# Intermediate_LCL_Top_20230320.net
KiCad netlist of a schematic drawn in Altium Designer
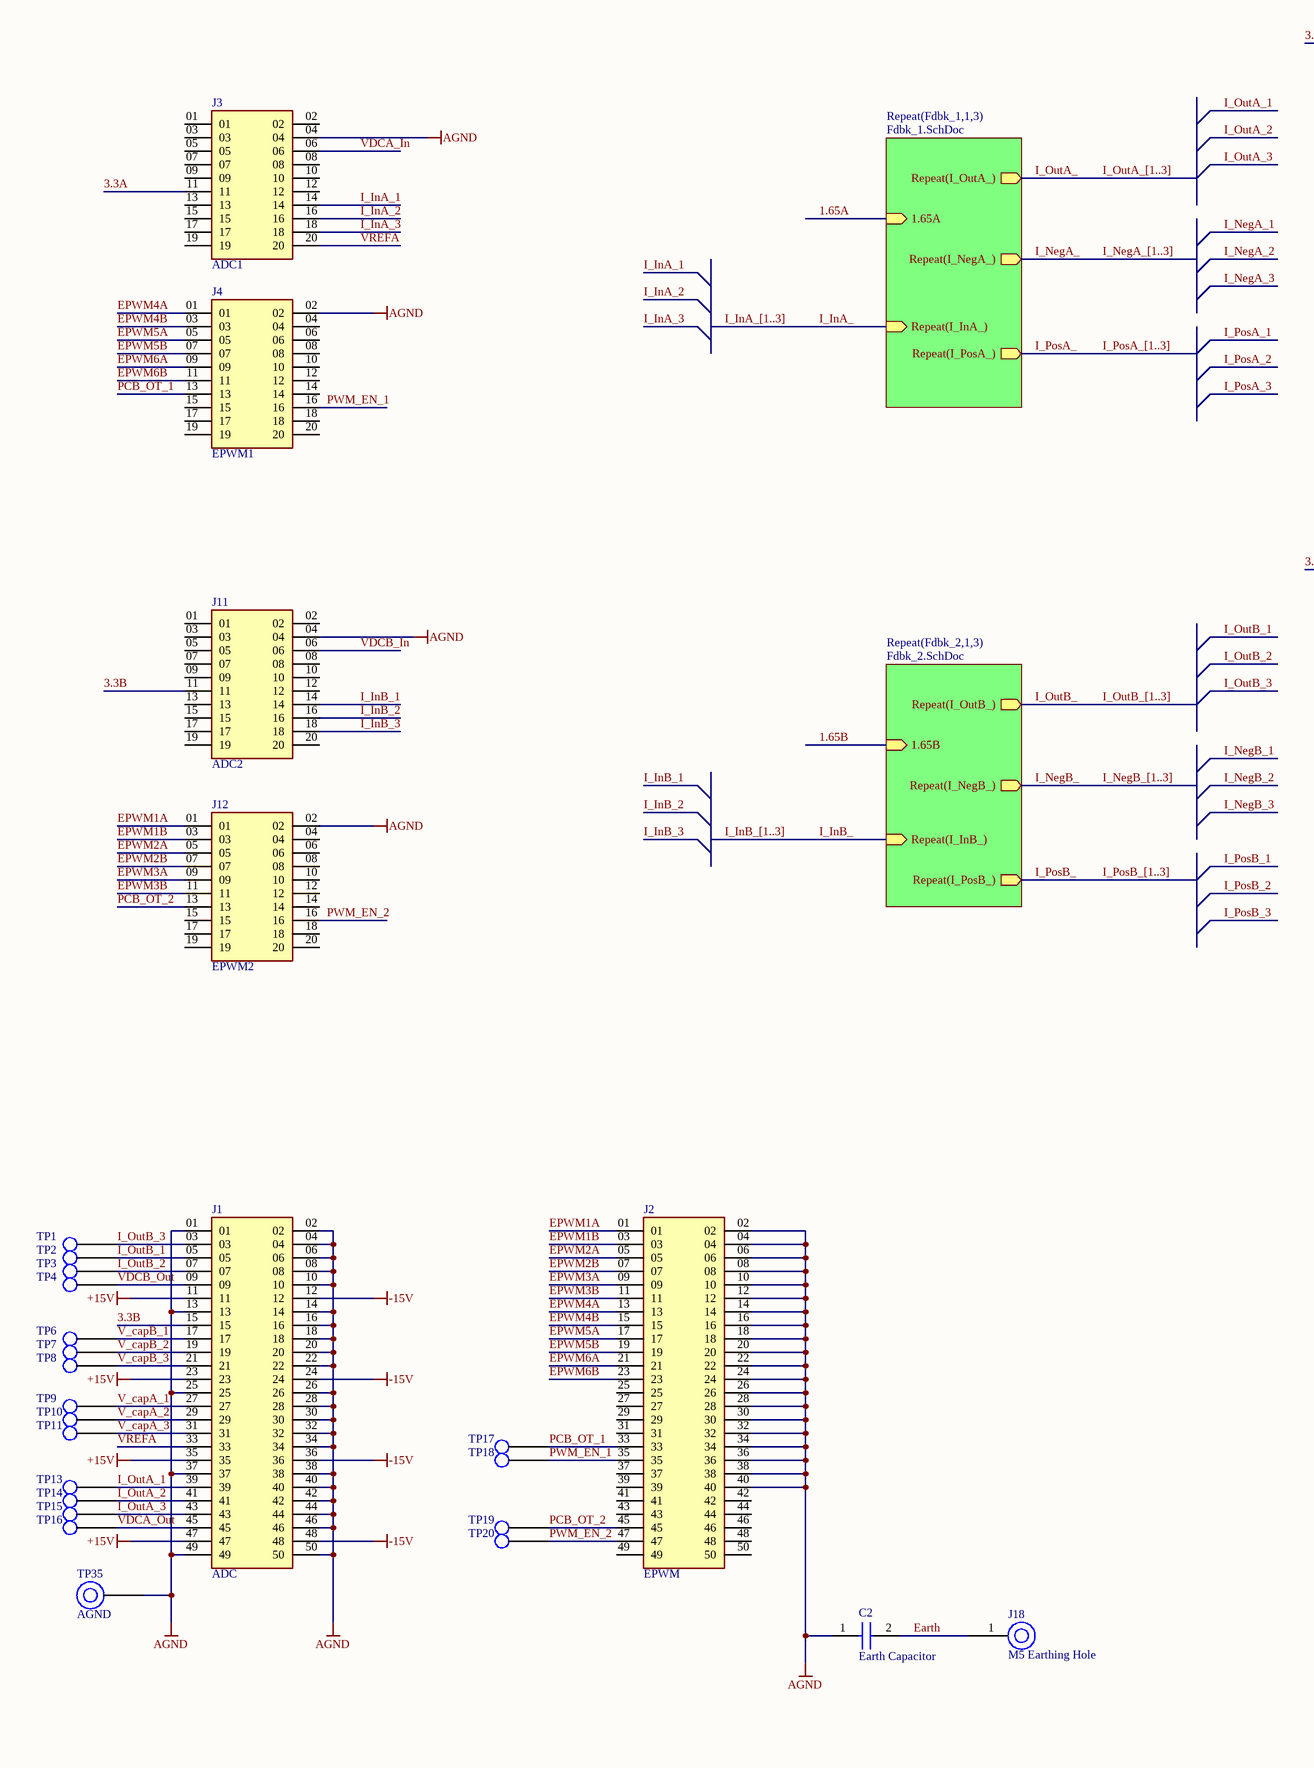
[diagram p0: Intermediate_LCL_Top_20230320.SchDoc, left]
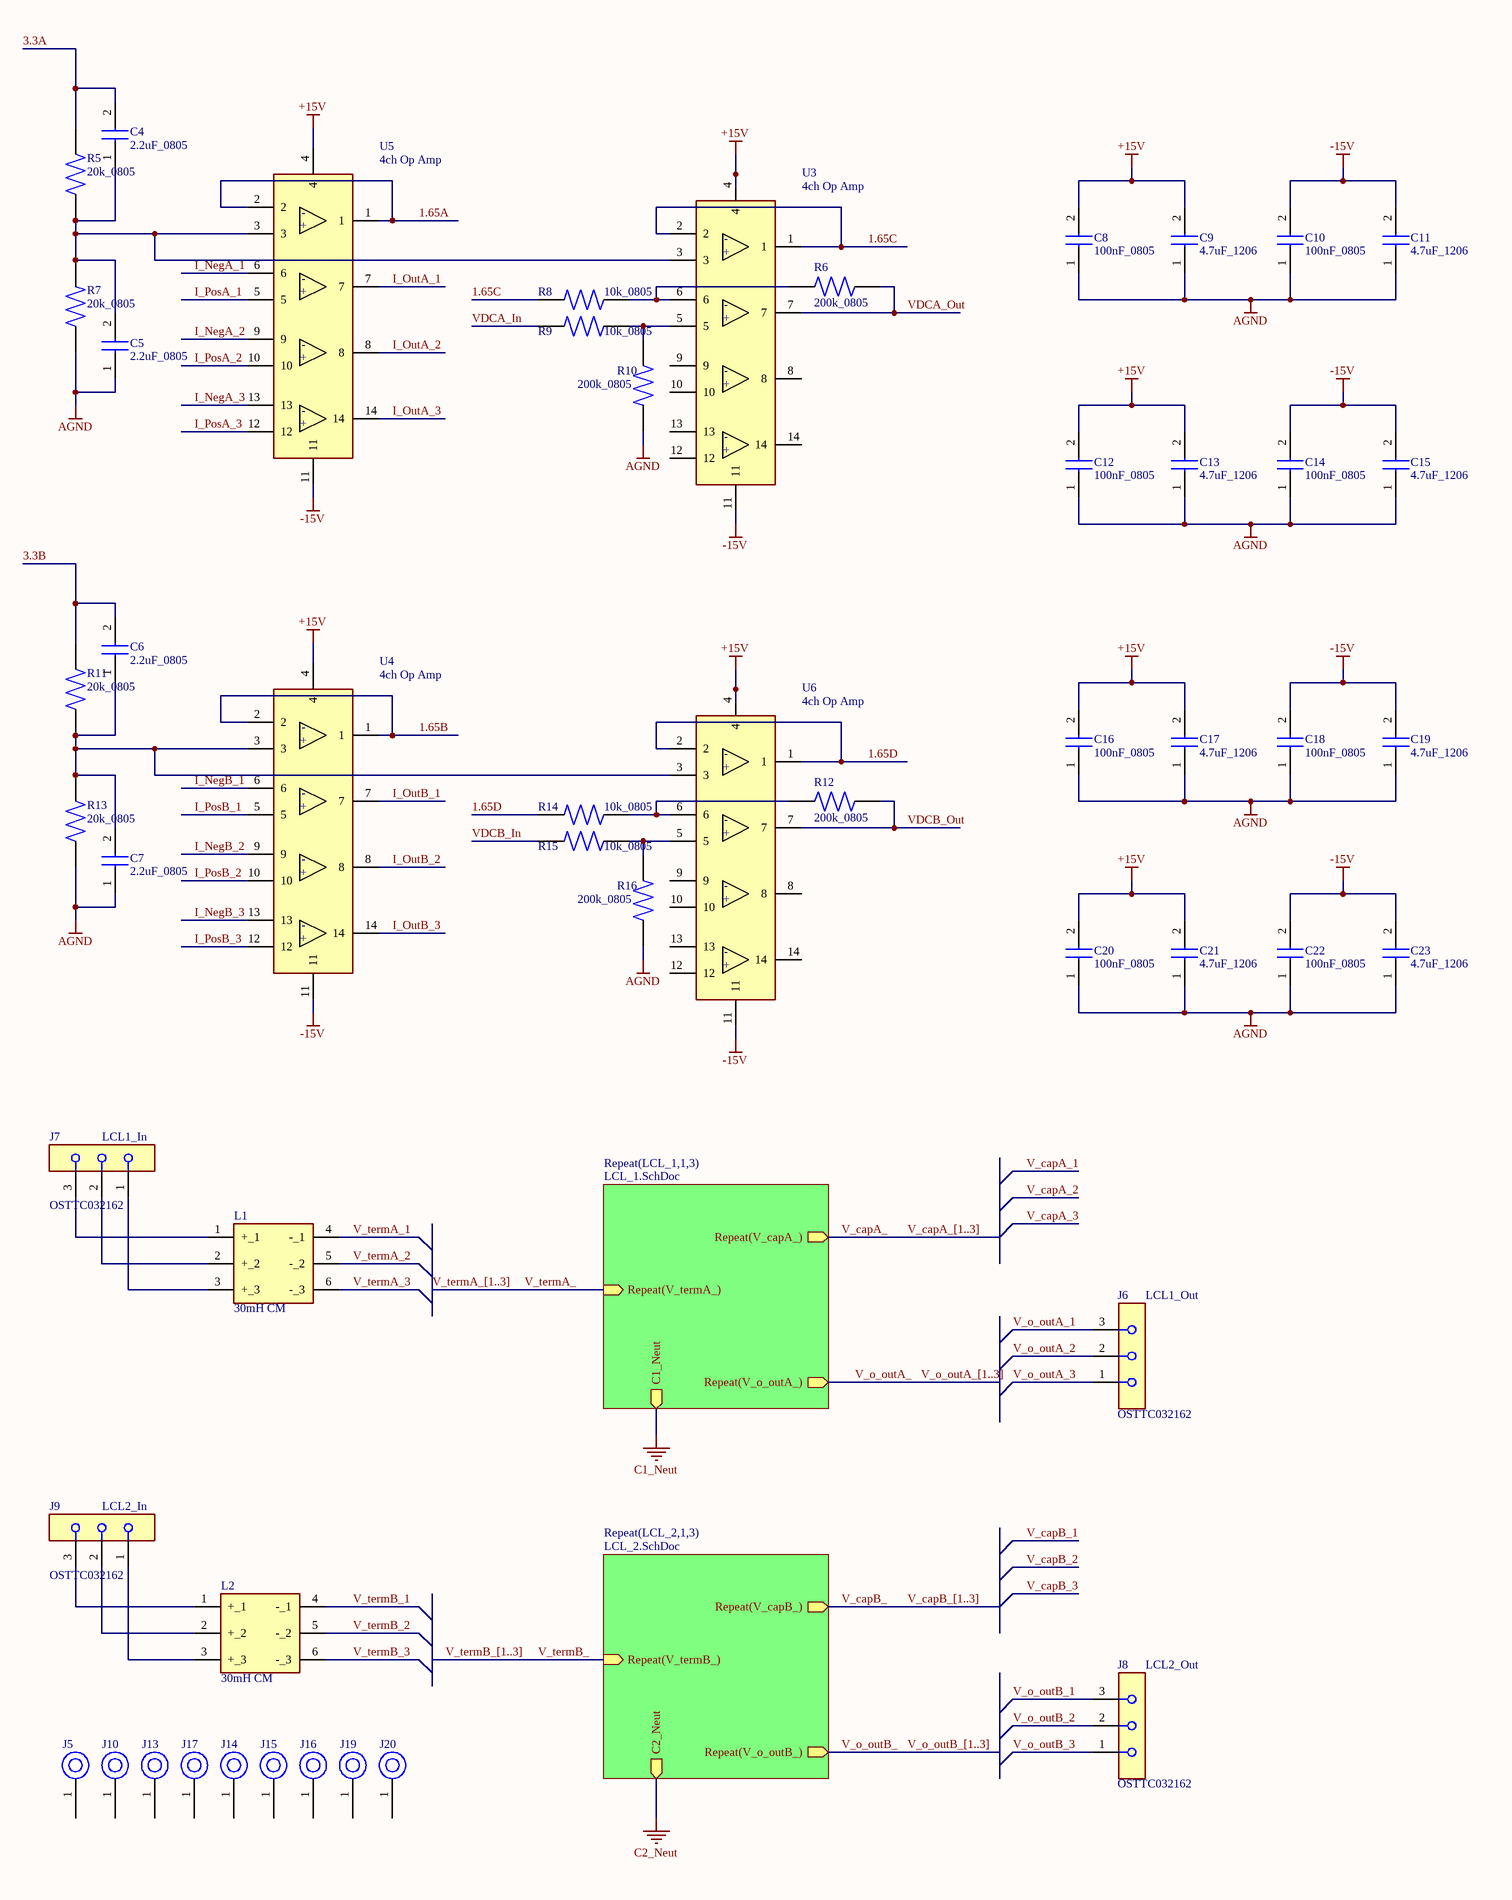
[diagram p1: Intermediate_LCL_Top_20230320.SchDoc, right]

(export (version "E")
  (design (tool "Eeschema 10.0.6"))
  (components
    (comp (ref "C2")
      (value "Earth Capacitor")
      (footprint "RAD-0.3")
      (description "Y Earth Capacitor")
      (fields (field (name "MP") "C1206C120J5GACTU"))
      (libsource (lib "FYP_Components") (part "102_Y"))
    )
    (comp (ref "C4")
      (value "2.2uF_0805")
      (footprint "0805 Capacitor")
      (description "SMD Multilayer Ceramic Capacitor, 2.2 µF, 50 V, 0805 [2012 Metric], ± 10%, X5R, C")
      (libsource (lib "FYP_Components") (part "C2012X5R1H225K125AB"))
    )
    (comp (ref "C5")
      (value "2.2uF_0805")
      (footprint "0805 Capacitor")
      (description "SMD Multilayer Ceramic Capacitor, 2.2 µF, 50 V, 0805 [2012 Metric], ± 10%, X5R, C")
      (libsource (lib "FYP_Components") (part "C2012X5R1H225K125AB"))
    )
    (comp (ref "C6")
      (value "2.2uF_0805")
      (footprint "0805 Capacitor")
      (description "SMD Multilayer Ceramic Capacitor, 2.2 µF, 50 V, 0805 [2012 Metric], ± 10%, X5R, C")
      (libsource (lib "FYP_Components") (part "C2012X5R1H225K125AB"))
    )
    (comp (ref "C7")
      (value "2.2uF_0805")
      (footprint "0805 Capacitor")
      (description "SMD Multilayer Ceramic Capacitor, 2.2 µF, 50 V, 0805 [2012 Metric], ± 10%, X5R, C")
      (libsource (lib "FYP_Components") (part "C2012X5R1H225K125AB"))
    )
    (comp (ref "C8")
      (value "100nF_0805")
      (footprint "0805 Capacitor")
      (description "SMD Multilayer Ceramic Capacitor, 0.1 µF, 50 V, 0805 [2012 Metric], ± 5%, X7R, C Series KEMET")
      (libsource (lib "FYP_Components") (part "C0805C104J5RACTU"))
    )
    (comp (ref "C9")
      (value "4.7uF_1206")
      (footprint "FYP_Components:1206 Capacitor")
      (description "SMD Multilayer Ceramic Capacitor, 4.7 µF, 50 V, 1206 [3216 Metric], ± 10%, X7R, C")
      (fields (field (name "MP") "C1206C120J5GACTU"))
      (libsource (lib "FYP_Components") (part "C3216X7R1H475K160AC"))
    )
    (comp (ref "C10")
      (value "100nF_0805")
      (footprint "0805 Capacitor")
      (description "SMD Multilayer Ceramic Capacitor, 0.1 µF, 50 V, 0805 [2012 Metric], ± 5%, X7R, C Series KEMET")
      (libsource (lib "FYP_Components") (part "C0805C104J5RACTU"))
    )
    (comp (ref "C11")
      (value "4.7uF_1206")
      (footprint "FYP_Components:1206 Capacitor")
      (description "SMD Multilayer Ceramic Capacitor, 4.7 µF, 50 V, 1206 [3216 Metric], ± 10%, X7R, C")
      (fields (field (name "MP") "C1206C120J5GACTU"))
      (libsource (lib "FYP_Components") (part "C3216X7R1H475K160AC"))
    )
    (comp (ref "C12")
      (value "100nF_0805")
      (footprint "0805 Capacitor")
      (description "SMD Multilayer Ceramic Capacitor, 0.1 µF, 50 V, 0805 [2012 Metric], ± 5%, X7R, C Series KEMET")
      (libsource (lib "FYP_Components") (part "C0805C104J5RACTU"))
    )
    (comp (ref "C13")
      (value "4.7uF_1206")
      (footprint "FYP_Components:1206 Capacitor")
      (description "SMD Multilayer Ceramic Capacitor, 4.7 µF, 50 V, 1206 [3216 Metric], ± 10%, X7R, C")
      (fields (field (name "MP") "C1206C120J5GACTU"))
      (libsource (lib "FYP_Components") (part "C3216X7R1H475K160AC"))
    )
    (comp (ref "C14")
      (value "100nF_0805")
      (footprint "0805 Capacitor")
      (description "SMD Multilayer Ceramic Capacitor, 0.1 µF, 50 V, 0805 [2012 Metric], ± 5%, X7R, C Series KEMET")
      (libsource (lib "FYP_Components") (part "C0805C104J5RACTU"))
    )
    (comp (ref "C15")
      (value "4.7uF_1206")
      (footprint "FYP_Components:1206 Capacitor")
      (description "SMD Multilayer Ceramic Capacitor, 4.7 µF, 50 V, 1206 [3216 Metric], ± 10%, X7R, C")
      (fields (field (name "MP") "C1206C120J5GACTU"))
      (libsource (lib "FYP_Components") (part "C3216X7R1H475K160AC"))
    )
    (comp (ref "C16")
      (value "100nF_0805")
      (footprint "0805 Capacitor")
      (description "SMD Multilayer Ceramic Capacitor, 0.1 µF, 50 V, 0805 [2012 Metric], ± 5%, X7R, C Series KEMET")
      (libsource (lib "FYP_Components") (part "C0805C104J5RACTU"))
    )
    (comp (ref "C17")
      (value "4.7uF_1206")
      (footprint "FYP_Components:1206 Capacitor")
      (description "SMD Multilayer Ceramic Capacitor, 4.7 µF, 50 V, 1206 [3216 Metric], ± 10%, X7R, C")
      (fields (field (name "MP") "C1206C120J5GACTU"))
      (libsource (lib "FYP_Components") (part "C3216X7R1H475K160AC"))
    )
    (comp (ref "C18")
      (value "100nF_0805")
      (footprint "0805 Capacitor")
      (description "SMD Multilayer Ceramic Capacitor, 0.1 µF, 50 V, 0805 [2012 Metric], ± 5%, X7R, C Series KEMET")
      (libsource (lib "FYP_Components") (part "C0805C104J5RACTU"))
    )
    (comp (ref "C19")
      (value "4.7uF_1206")
      (footprint "FYP_Components:1206 Capacitor")
      (description "SMD Multilayer Ceramic Capacitor, 4.7 µF, 50 V, 1206 [3216 Metric], ± 10%, X7R, C")
      (fields (field (name "MP") "C1206C120J5GACTU"))
      (libsource (lib "FYP_Components") (part "C3216X7R1H475K160AC"))
    )
    (comp (ref "C20")
      (value "100nF_0805")
      (footprint "0805 Capacitor")
      (description "SMD Multilayer Ceramic Capacitor, 0.1 µF, 50 V, 0805 [2012 Metric], ± 5%, X7R, C Series KEMET")
      (libsource (lib "FYP_Components") (part "C0805C104J5RACTU"))
    )
    (comp (ref "C21")
      (value "4.7uF_1206")
      (footprint "FYP_Components:1206 Capacitor")
      (description "SMD Multilayer Ceramic Capacitor, 4.7 µF, 50 V, 1206 [3216 Metric], ± 10%, X7R, C")
      (fields (field (name "MP") "C1206C120J5GACTU"))
      (libsource (lib "FYP_Components") (part "C3216X7R1H475K160AC"))
    )
    (comp (ref "C22")
      (value "100nF_0805")
      (footprint "0805 Capacitor")
      (description "SMD Multilayer Ceramic Capacitor, 0.1 µF, 50 V, 0805 [2012 Metric], ± 5%, X7R, C Series KEMET")
      (libsource (lib "FYP_Components") (part "C0805C104J5RACTU"))
    )
    (comp (ref "C23")
      (value "4.7uF_1206")
      (footprint "FYP_Components:1206 Capacitor")
      (description "SMD Multilayer Ceramic Capacitor, 4.7 µF, 50 V, 1206 [3216 Metric], ± 10%, X7R, C")
      (fields (field (name "MP") "C1206C120J5GACTU"))
      (libsource (lib "FYP_Components") (part "C3216X7R1H475K160AC"))
    )
    (comp (ref "J1")
      (value "ADC")
      (footprint "SHF-125-01-L-D-RA")
      (description "50-Pin Simplus Connector")
      (fields (field (name "MP") "SHF-125-01-L-D-RA") (field (name "MF") "Samtec"))
      (libsource (lib "FYP_Components") (part "SHF-125-01-L-D-RA"))
    )
    (comp (ref "J2")
      (value "EPWM")
      (footprint "SHF-125-01-L-D-RA")
      (description "50-Pin Simplus Connector")
      (fields (field (name "MP") "SHF-125-01-L-D-RA") (field (name "MF") "Samtec"))
      (libsource (lib "FYP_Components") (part "SHF-125-01-L-D-RA"))
    )
    (comp (ref "J3")
      (value "ADC1")
      (footprint "FYP_Components:SSQ-110-03-T-D")
      (description "SSQ - Samtec 2.54mm Square Tail Dual Row Socket Strip 8.5mm Profile - Fast Stock")
      (fields (field (name "MF") "Samtec Inc.") (field (name "MP") "SSQ-110-03-T-D"))
      (libsource (lib "FYP_Components") (part "SSQ-110-03-T-D"))
    )
    (comp (ref "J4")
      (value "EPWM1")
      (footprint "FYP_Components:SSQ-110-03-T-D")
      (description "SSQ - Samtec 2.54mm Square Tail Dual Row Socket Strip 8.5mm Profile - Fast Stock")
      (fields (field (name "MF") "Samtec Inc.") (field (name "MP") "SSQ-110-03-T-D"))
      (libsource (lib "FYP_Components") (part "SSQ-110-03-T-D"))
    )
    (comp (ref "J5")
      (value "M5 Mounting Hole")
      (footprint "M5 Mounting Hole")
      (libsource (lib "FYP_Components") (part "M5 Mounting Hole"))
    )
    (comp (ref "J6")
      (value "LCL1_Out")
      (footprint "3 Pin Terminal")
      (description "3 Position Terminal Block 5.08mm")
      (fields
        (field (name "VOLTAGE") "300V")
        (field (name "MANUFACTURER") "On Shore Technology")
        (field (name "PART NUMBER") "OSTTC032162")
      )
      (libsource (lib "FYP_Components") (part "3PinTerminal"))
    )
    (comp (ref "J7")
      (value "LCL1_In")
      (footprint "3 Pin Terminal")
      (description "3 Position Terminal Block 5.08mm")
      (fields
        (field (name "VOLTAGE") "300V")
        (field (name "MANUFACTURER") "On Shore Technology")
        (field (name "PART NUMBER") "OSTTC032162")
      )
      (libsource (lib "") (part "3PinTerminal_1"))
    )
    (comp (ref "J8")
      (value "LCL2_Out")
      (footprint "3 Pin Terminal")
      (description "3 Position Terminal Block 5.08mm")
      (fields
        (field (name "VOLTAGE") "300V")
        (field (name "MANUFACTURER") "On Shore Technology")
        (field (name "PART NUMBER") "OSTTC032162")
      )
      (libsource (lib "FYP_Components") (part "3PinTerminal"))
    )
    (comp (ref "J9")
      (value "LCL2_In")
      (footprint "3 Pin Terminal")
      (description "3 Position Terminal Block 5.08mm")
      (fields
        (field (name "VOLTAGE") "300V")
        (field (name "MANUFACTURER") "On Shore Technology")
        (field (name "PART NUMBER") "OSTTC032162")
      )
      (libsource (lib "") (part "3PinTerminal_1"))
    )
    (comp (ref "J10")
      (value "M5 Mounting Hole")
      (footprint "M5 Mounting Hole")
      (libsource (lib "FYP_Components") (part "M5 Mounting Hole"))
    )
    (comp (ref "J11")
      (value "ADC2")
      (footprint "FYP_Components:SSQ-110-03-T-D")
      (description "SSQ - Samtec 2.54mm Square Tail Dual Row Socket Strip 8.5mm Profile - Fast Stock")
      (fields (field (name "MF") "Samtec Inc.") (field (name "MP") "SSQ-110-03-T-D"))
      (libsource (lib "FYP_Components") (part "SSQ-110-03-T-D"))
    )
    (comp (ref "J12")
      (value "EPWM2")
      (footprint "FYP_Components:SSQ-110-03-T-D")
      (description "SSQ - Samtec 2.54mm Square Tail Dual Row Socket Strip 8.5mm Profile - Fast Stock")
      (fields (field (name "MF") "Samtec Inc.") (field (name "MP") "SSQ-110-03-T-D"))
      (libsource (lib "FYP_Components") (part "SSQ-110-03-T-D"))
    )
    (comp (ref "J13")
      (value "M5 Mounting Hole")
      (footprint "M5 Mounting Hole")
      (libsource (lib "FYP_Components") (part "M5 Mounting Hole"))
    )
    (comp (ref "J14")
      (value "M5 Mounting Hole")
      (footprint "M5 Mounting Hole")
      (libsource (lib "FYP_Components") (part "M5 Mounting Hole"))
    )
    (comp (ref "J15")
      (value "M5 Mounting Hole")
      (footprint "M5 Mounting Hole")
      (libsource (lib "FYP_Components") (part "M5 Mounting Hole"))
    )
    (comp (ref "J16")
      (value "M5 Mounting Hole")
      (footprint "M5 Mounting Hole")
      (libsource (lib "FYP_Components") (part "M5 Mounting Hole"))
    )
    (comp (ref "J17")
      (value "M5 Mounting Hole")
      (footprint "M5 Mounting Hole")
      (libsource (lib "FYP_Components") (part "M5 Mounting Hole"))
    )
    (comp (ref "J18")
      (value "M5 Earthing Hole")
      (footprint "M5 Earthing Hole")
      (libsource (lib "FYP_Components") (part "M5 Earthing Hole"))
    )
    (comp (ref "J19")
      (value "M5 Mounting Hole")
      (footprint "M5 Mounting Hole")
      (libsource (lib "FYP_Components") (part "M5 Mounting Hole"))
    )
    (comp (ref "J20")
      (value "M5 Mounting Hole")
      (footprint "M5 Mounting Hole")
      (libsource (lib "FYP_Components") (part "M5 Mounting Hole"))
    )
    (comp (ref "L1")
      (value "30mH CM")
      (footprint "FYP_Components:CM Choke Custom")
      (description "30mH Custom CM Choke")
      (fields
        (field (name "MANUFACTURER_PART_NUMBER") "744839029220")
        (field (name "MOUSER PART NUMBER") "710-744839029220")
      )
      (libsource (lib "FYP_Components") (part "30mH Custom CM Choke"))
    )
    (comp (ref "L2")
      (value "30mH CM")
      (footprint "FYP_Components:CM Choke Custom")
      (description "30mH Custom CM Choke")
      (fields
        (field (name "MANUFACTURER_PART_NUMBER") "744839029220")
        (field (name "MOUSER PART NUMBER") "710-744839029220")
      )
      (libsource (lib "FYP_Components") (part "30mH Custom CM Choke"))
    )
    (comp (ref "R5")
      (value "20k_0805")
      (footprint "FYP_Components:0805 Resistor")
      (description "SMD Chip Resistor, 20 kohm, ± 1%, 125 mW, 0805 [2012 Metric], Thick Film, General Purpose")
      (fields (field (name "MF") "Bourns") (field (name "MP") "CRE2512-FZ-R007E-3"))
      (libsource (lib "FYP_Components") (part "CRCW080520K0FKEA"))
    )
    (comp (ref "R6")
      (value "200k_0805")
      (footprint "FYP_Components:0805 Resistor")
      (description "SMD Chip Resistor, 200 kohm, ± 1%, 125 mW, 0805 [2012 Metric], Thick Film, General Purpose")
      (fields (field (name "MF") "Bourns") (field (name "MP") "CRE2512-FZ-R007E-3"))
      (libsource (lib "FYP_Components") (part "CRCW0805200KFKEA"))
    )
    (comp (ref "R7")
      (value "20k_0805")
      (footprint "FYP_Components:0805 Resistor")
      (description "SMD Chip Resistor, 20 kohm, ± 1%, 125 mW, 0805 [2012 Metric], Thick Film, General Purpose")
      (fields (field (name "MF") "Bourns") (field (name "MP") "CRE2512-FZ-R007E-3"))
      (libsource (lib "FYP_Components") (part "CRCW080520K0FKEA"))
    )
    (comp (ref "R8")
      (value "10k_0805")
      (footprint "FYP_Components:0805 Resistor")
      (description "SMD Chip Resistor, 10 kohm, ± 1%, 125 mW, 0805 [2012 Metric], Thick Film, General Purpose")
      (fields (field (name "MF") "Bourns") (field (name "MP") "CRE2512-FZ-R007E-3"))
      (libsource (lib "FYP_Components") (part "CRCW080510K0FKEA"))
    )
    (comp (ref "R9")
      (value "10k_0805")
      (footprint "FYP_Components:0805 Resistor")
      (description "SMD Chip Resistor, 10 kohm, ± 1%, 125 mW, 0805 [2012 Metric], Thick Film, General Purpose")
      (fields (field (name "MF") "Bourns") (field (name "MP") "CRE2512-FZ-R007E-3"))
      (libsource (lib "FYP_Components") (part "CRCW080510K0FKEA"))
    )
    (comp (ref "R10")
      (value "200k_0805")
      (footprint "FYP_Components:0805 Resistor")
      (description "SMD Chip Resistor, 200 kohm, ± 1%, 125 mW, 0805 [2012 Metric], Thick Film, General Purpose")
      (fields (field (name "MF") "Bourns") (field (name "MP") "CRE2512-FZ-R007E-3"))
      (libsource (lib "FYP_Components") (part "CRCW0805200KFKEA"))
    )
    (comp (ref "R11")
      (value "20k_0805")
      (footprint "FYP_Components:0805 Resistor")
      (description "SMD Chip Resistor, 20 kohm, ± 1%, 125 mW, 0805 [2012 Metric], Thick Film, General Purpose")
      (fields (field (name "MF") "Bourns") (field (name "MP") "CRE2512-FZ-R007E-3"))
      (libsource (lib "FYP_Components") (part "CRCW080520K0FKEA"))
    )
    (comp (ref "R12")
      (value "200k_0805")
      (footprint "FYP_Components:0805 Resistor")
      (description "SMD Chip Resistor, 200 kohm, ± 1%, 125 mW, 0805 [2012 Metric], Thick Film, General Purpose")
      (fields (field (name "MF") "Bourns") (field (name "MP") "CRE2512-FZ-R007E-3"))
      (libsource (lib "FYP_Components") (part "CRCW0805200KFKEA"))
    )
    (comp (ref "R13")
      (value "20k_0805")
      (footprint "FYP_Components:0805 Resistor")
      (description "SMD Chip Resistor, 20 kohm, ± 1%, 125 mW, 0805 [2012 Metric], Thick Film, General Purpose")
      (fields (field (name "MF") "Bourns") (field (name "MP") "CRE2512-FZ-R007E-3"))
      (libsource (lib "FYP_Components") (part "CRCW080520K0FKEA"))
    )
    (comp (ref "R14")
      (value "10k_0805")
      (footprint "FYP_Components:0805 Resistor")
      (description "SMD Chip Resistor, 10 kohm, ± 1%, 125 mW, 0805 [2012 Metric], Thick Film, General Purpose")
      (fields (field (name "MF") "Bourns") (field (name "MP") "CRE2512-FZ-R007E-3"))
      (libsource (lib "FYP_Components") (part "CRCW080510K0FKEA"))
    )
    (comp (ref "R15")
      (value "10k_0805")
      (footprint "FYP_Components:0805 Resistor")
      (description "SMD Chip Resistor, 10 kohm, ± 1%, 125 mW, 0805 [2012 Metric], Thick Film, General Purpose")
      (fields (field (name "MF") "Bourns") (field (name "MP") "CRE2512-FZ-R007E-3"))
      (libsource (lib "FYP_Components") (part "CRCW080510K0FKEA"))
    )
    (comp (ref "R16")
      (value "200k_0805")
      (footprint "FYP_Components:0805 Resistor")
      (description "SMD Chip Resistor, 200 kohm, ± 1%, 125 mW, 0805 [2012 Metric], Thick Film, General Purpose")
      (fields (field (name "MF") "Bourns") (field (name "MP") "CRE2512-FZ-R007E-3"))
      (libsource (lib "FYP_Components") (part "CRCW0805200KFKEA"))
    )
    (comp (ref "TP1")
      (value "I3")
      (footprint "PCB 1.32mm TestPoint")
      (description "20-313143 PCB Test Point, White, Through Hole Mount, 1.32 mm, Phosphor Bronze, Tin Plated Contacts")
      (libsource (lib "FYP_Components") (part "PCBTestpoint"))
    )
    (comp (ref "TP2")
      (value "I1")
      (footprint "PCB 1.32mm TestPoint")
      (description "20-313143 PCB Test Point, White, Through Hole Mount, 1.32 mm, Phosphor Bronze, Tin Plated Contacts")
      (libsource (lib "FYP_Components") (part "PCBTestpoint"))
    )
    (comp (ref "TP3")
      (value "I2")
      (footprint "PCB 1.32mm TestPoint")
      (description "20-313143 PCB Test Point, White, Through Hole Mount, 1.32 mm, Phosphor Bronze, Tin Plated Contacts")
      (libsource (lib "FYP_Components") (part "PCBTestpoint"))
    )
    (comp (ref "TP4")
      (value "VDC")
      (footprint "PCB 1.32mm TestPoint")
      (description "20-313143 PCB Test Point, White, Through Hole Mount, 1.32 mm, Phosphor Bronze, Tin Plated Contacts")
      (libsource (lib "FYP_Components") (part "PCBTestpoint"))
    )
    (comp (ref "TP6")
      (value "VC_2A")
      (footprint "PCB 1.32mm TestPoint")
      (description "20-313143 PCB Test Point, White, Through Hole Mount, 1.32 mm, Phosphor Bronze, Tin Plated Contacts")
      (libsource (lib "FYP_Components") (part "PCBTestpoint"))
    )
    (comp (ref "TP7")
      (value "VC_2B")
      (footprint "PCB 1.32mm TestPoint")
      (description "20-313143 PCB Test Point, White, Through Hole Mount, 1.32 mm, Phosphor Bronze, Tin Plated Contacts")
      (libsource (lib "FYP_Components") (part "PCBTestpoint"))
    )
    (comp (ref "TP8")
      (value "VC_2C")
      (footprint "PCB 1.32mm TestPoint")
      (description "20-313143 PCB Test Point, White, Through Hole Mount, 1.32 mm, Phosphor Bronze, Tin Plated Contacts")
      (libsource (lib "FYP_Components") (part "PCBTestpoint"))
    )
    (comp (ref "TP9")
      (value "VC_1A")
      (footprint "PCB 1.32mm TestPoint")
      (description "20-313143 PCB Test Point, White, Through Hole Mount, 1.32 mm, Phosphor Bronze, Tin Plated Contacts")
      (libsource (lib "FYP_Components") (part "PCBTestpoint"))
    )
    (comp (ref "TP10")
      (value "VC_1B")
      (footprint "PCB 1.32mm TestPoint")
      (description "20-313143 PCB Test Point, White, Through Hole Mount, 1.32 mm, Phosphor Bronze, Tin Plated Contacts")
      (libsource (lib "FYP_Components") (part "PCBTestpoint"))
    )
    (comp (ref "TP11")
      (value "VC_1C")
      (footprint "PCB 1.32mm TestPoint")
      (description "20-313143 PCB Test Point, White, Through Hole Mount, 1.32 mm, Phosphor Bronze, Tin Plated Contacts")
      (libsource (lib "FYP_Components") (part "PCBTestpoint"))
    )
    (comp (ref "TP13")
      (value "I1")
      (footprint "PCB 1.32mm TestPoint")
      (description "20-313143 PCB Test Point, White, Through Hole Mount, 1.32 mm, Phosphor Bronze, Tin Plated Contacts")
      (libsource (lib "FYP_Components") (part "PCBTestpoint"))
    )
    (comp (ref "TP14")
      (value "I2")
      (footprint "PCB 1.32mm TestPoint")
      (description "20-313143 PCB Test Point, White, Through Hole Mount, 1.32 mm, Phosphor Bronze, Tin Plated Contacts")
      (libsource (lib "FYP_Components") (part "PCBTestpoint"))
    )
    (comp (ref "TP15")
      (value "I3")
      (footprint "PCB 1.32mm TestPoint")
      (description "20-313143 PCB Test Point, White, Through Hole Mount, 1.32 mm, Phosphor Bronze, Tin Plated Contacts")
      (libsource (lib "FYP_Components") (part "PCBTestpoint"))
    )
    (comp (ref "TP16")
      (value "VDC")
      (footprint "PCB 1.32mm TestPoint")
      (description "20-313143 PCB Test Point, White, Through Hole Mount, 1.32 mm, Phosphor Bronze, Tin Plated Contacts")
      (libsource (lib "FYP_Components") (part "PCBTestpoint"))
    )
    (comp (ref "TP17")
      (value "OT1")
      (footprint "PCB 1.32mm TestPoint")
      (description "20-313143 PCB Test Point, White, Through Hole Mount, 1.32 mm, Phosphor Bronze, Tin Plated Contacts")
      (libsource (lib "FYP_Components") (part "PCBTestpoint"))
    )
    (comp (ref "TP18")
      (value "PWMEN1")
      (footprint "PCB 1.32mm TestPoint")
      (description "20-313143 PCB Test Point, White, Through Hole Mount, 1.32 mm, Phosphor Bronze, Tin Plated Contacts")
      (libsource (lib "FYP_Components") (part "PCBTestpoint"))
    )
    (comp (ref "TP19")
      (value "OT2")
      (footprint "PCB 1.32mm TestPoint")
      (description "20-313143 PCB Test Point, White, Through Hole Mount, 1.32 mm, Phosphor Bronze, Tin Plated Contacts")
      (libsource (lib "FYP_Components") (part "PCBTestpoint"))
    )
    (comp (ref "TP20")
      (value "PWMEN2")
      (footprint "PCB 1.32mm TestPoint")
      (description "20-313143 PCB Test Point, White, Through Hole Mount, 1.32 mm, Phosphor Bronze, Tin Plated Contacts")
      (libsource (lib "FYP_Components") (part "PCBTestpoint"))
    )
    (comp (ref "TP35")
      (value "AGND")
      (footprint "1.9mm Hole")
      (description "H2182-01 PCB Test Point, PCB Mount, 1.9 mm, Brass, Tin Plated Contacts")
      (libsource (lib "FYP_Components") (part "GroundTestPoint"))
    )
    (comp (ref "U3")
      (value "4ch Op Amp")
      (footprint "SOIC-14")
      (description "Quad, 30-V, 3-MHz, high slew rate (13-V/µs), In to V+, JFET-input op amp")
      (libsource (lib "FYP_Components") (part "TL074D"))
    )
    (comp (ref "U4")
      (value "4ch Op Amp")
      (footprint "SOIC-14")
      (description "Quad, 30-V, 3-MHz, high slew rate (13-V/µs), In to V+, JFET-input op amp")
      (libsource (lib "FYP_Components") (part "TL074D"))
    )
    (comp (ref "U5")
      (value "4ch Op Amp")
      (footprint "SOIC-14")
      (description "Quad, 30-V, 3-MHz, high slew rate (13-V/µs), In to V+, JFET-input op amp")
      (libsource (lib "FYP_Components") (part "TL074D"))
    )
    (comp (ref "U6")
      (value "4ch Op Amp")
      (footprint "SOIC-14")
      (description "Quad, 30-V, 3-MHz, high slew rate (13-V/µs), In to V+, JFET-input op amp")
      (libsource (lib "FYP_Components") (part "TL074D"))
    )
  )
  (nets
    (net (code "1") (name "+15V") (class "Default")
      (node (ref "C12") (pin "2") (pinfunction "2_2") (pintype "passive"))
      (node (ref "C13") (pin "2") (pinfunction "2_2") (pintype "passive"))
      (node (ref "C16") (pin "2") (pinfunction "2_2") (pintype "passive"))
      (node (ref "C17") (pin "2") (pinfunction "2_2") (pintype "passive"))
      (node (ref "C20") (pin "2") (pinfunction "2_2") (pintype "passive"))
      (node (ref "C21") (pin "2") (pinfunction "2_2") (pintype "passive"))
      (node (ref "C8") (pin "2") (pinfunction "2_2") (pintype "passive"))
      (node (ref "C9") (pin "2") (pinfunction "2_2") (pintype "passive"))
      (node (ref "J1") (pin "11") (pinfunction "11_11") (pintype "passive"))
      (node (ref "J1") (pin "23") (pinfunction "23_23") (pintype "passive"))
      (node (ref "J1") (pin "35") (pinfunction "35_35") (pintype "passive"))
      (node (ref "J1") (pin "47") (pinfunction "47_47") (pintype "passive"))
      (node (ref "U3") (pin "4") (pinfunction "4_4") (pintype "passive"))
      (node (ref "U4") (pin "4") (pinfunction "4_4") (pintype "passive"))
      (node (ref "U5") (pin "4") (pinfunction "4_4") (pintype "passive"))
      (node (ref "U6") (pin "4") (pinfunction "4_4") (pintype "passive"))
    )
    (net (code "2") (name "-15V") (class "Default")
      (node (ref "C10") (pin "2") (pinfunction "2_2") (pintype "passive"))
      (node (ref "C11") (pin "2") (pinfunction "2_2") (pintype "passive"))
      (node (ref "C14") (pin "2") (pinfunction "2_2") (pintype "passive"))
      (node (ref "C15") (pin "2") (pinfunction "2_2") (pintype "passive"))
      (node (ref "C18") (pin "2") (pinfunction "2_2") (pintype "passive"))
      (node (ref "C19") (pin "2") (pinfunction "2_2") (pintype "passive"))
      (node (ref "C22") (pin "2") (pinfunction "2_2") (pintype "passive"))
      (node (ref "C23") (pin "2") (pinfunction "2_2") (pintype "passive"))
      (node (ref "J1") (pin "12") (pinfunction "12_12") (pintype "passive"))
      (node (ref "J1") (pin "24") (pinfunction "24_24") (pintype "passive"))
      (node (ref "J1") (pin "36") (pinfunction "36_36") (pintype "passive"))
      (node (ref "J1") (pin "48") (pinfunction "48_48") (pintype "passive"))
      (node (ref "U3") (pin "11") (pinfunction "11_11") (pintype "passive"))
      (node (ref "U4") (pin "11") (pinfunction "11_11") (pintype "passive"))
      (node (ref "U5") (pin "11") (pinfunction "11_11") (pintype "passive"))
      (node (ref "U6") (pin "11") (pinfunction "11_11") (pintype "passive"))
    )
    (net (code "3") (name "/1.65A") (class "Default")
      (node (ref "U5") (pin "1") (pinfunction "1_1") (pintype "passive"))
      (node (ref "U5") (pin "2") (pinfunction "2_2") (pintype "passive"))
    )
    (net (code "4") (name "/1.65B") (class "Default")
      (node (ref "U4") (pin "1") (pinfunction "1_1") (pintype "passive"))
      (node (ref "U4") (pin "2") (pinfunction "2_2") (pintype "passive"))
    )
    (net (code "5") (name "/1.65C") (class "Default")
      (node (ref "R8") (pin "1") (pinfunction "1_1") (pintype "passive"))
      (node (ref "U3") (pin "1") (pinfunction "1_1") (pintype "passive"))
      (node (ref "U3") (pin "2") (pinfunction "2_2") (pintype "passive"))
    )
    (net (code "6") (name "/1.65D") (class "Default")
      (node (ref "R14") (pin "1") (pinfunction "1_1") (pintype "passive"))
      (node (ref "U6") (pin "1") (pinfunction "1_1") (pintype "passive"))
      (node (ref "U6") (pin "2") (pinfunction "2_2") (pintype "passive"))
    )
    (net (code "7") (name "/3.3A") (class "Default")
      (node (ref "C4") (pin "2") (pinfunction "2_2") (pintype "passive"))
      (node (ref "J3") (pin "11") (pinfunction "11_11") (pintype "passive"))
      (node (ref "R5") (pin "2") (pinfunction "2_2") (pintype "passive"))
    )
    (net (code "8") (name "/3.3B") (class "Default")
      (node (ref "C6") (pin "2") (pinfunction "2_2") (pintype "passive"))
      (node (ref "J1") (pin "15") (pinfunction "15_15") (pintype "passive"))
      (node (ref "J11") (pin "11") (pinfunction "11_11") (pintype "passive"))
      (node (ref "R11") (pin "2") (pinfunction "2_2") (pintype "passive"))
    )
    (net (code "9") (name "/EPWM1A") (class "Default")
      (node (ref "J12") (pin "01") (pinfunction "01_01") (pintype "passive"))
      (node (ref "J2") (pin "01") (pinfunction "01_01") (pintype "passive"))
    )
    (net (code "10") (name "/EPWM1B") (class "Default")
      (node (ref "J12") (pin "03") (pinfunction "03_03") (pintype "passive"))
      (node (ref "J2") (pin "03") (pinfunction "03_03") (pintype "passive"))
    )
    (net (code "11") (name "/EPWM2A") (class "Default")
      (node (ref "J12") (pin "05") (pinfunction "05_05") (pintype "passive"))
      (node (ref "J2") (pin "05") (pinfunction "05_05") (pintype "passive"))
    )
    (net (code "12") (name "/EPWM2B") (class "Default")
      (node (ref "J12") (pin "07") (pinfunction "07_07") (pintype "passive"))
      (node (ref "J2") (pin "07") (pinfunction "07_07") (pintype "passive"))
    )
    (net (code "13") (name "/EPWM3A") (class "Default")
      (node (ref "J12") (pin "09") (pinfunction "09_09") (pintype "passive"))
      (node (ref "J2") (pin "09") (pinfunction "09_09") (pintype "passive"))
    )
    (net (code "14") (name "/EPWM3B") (class "Default")
      (node (ref "J12") (pin "11") (pinfunction "11_11") (pintype "passive"))
      (node (ref "J2") (pin "11") (pinfunction "11_11") (pintype "passive"))
    )
    (net (code "15") (name "/EPWM4A") (class "Default")
      (node (ref "J2") (pin "13") (pinfunction "13_13") (pintype "passive"))
      (node (ref "J4") (pin "01") (pinfunction "01_01") (pintype "passive"))
    )
    (net (code "16") (name "/EPWM4B") (class "Default")
      (node (ref "J2") (pin "15") (pinfunction "15_15") (pintype "passive"))
      (node (ref "J4") (pin "03") (pinfunction "03_03") (pintype "passive"))
    )
    (net (code "17") (name "/EPWM5A") (class "Default")
      (node (ref "J2") (pin "17") (pinfunction "17_17") (pintype "passive"))
      (node (ref "J4") (pin "05") (pinfunction "05_05") (pintype "passive"))
    )
    (net (code "18") (name "/EPWM5B") (class "Default")
      (node (ref "J2") (pin "19") (pinfunction "19_19") (pintype "passive"))
      (node (ref "J4") (pin "07") (pinfunction "07_07") (pintype "passive"))
    )
    (net (code "19") (name "/EPWM6A") (class "Default")
      (node (ref "J2") (pin "21") (pinfunction "21_21") (pintype "passive"))
      (node (ref "J4") (pin "09") (pinfunction "09_09") (pintype "passive"))
    )
    (net (code "20") (name "/EPWM6B") (class "Default")
      (node (ref "J2") (pin "23") (pinfunction "23_23") (pintype "passive"))
      (node (ref "J4") (pin "11") (pinfunction "11_11") (pintype "passive"))
    )
    (net (code "21") (name "/Earth") (class "Default")
      (node (ref "C2") (pin "2") (pinfunction "2_2") (pintype "passive"))
      (node (ref "J18") (pin "1") (pinfunction "1_1") (pintype "passive"))
    )
    (net (code "23") (name "/I_InA_1") (class "Default")
      (node (ref "J3") (pin "14") (pinfunction "14_14") (pintype "passive"))
    )
    (net (code "24") (name "/I_InA_2") (class "Default")
      (node (ref "J3") (pin "16") (pinfunction "16_16") (pintype "passive"))
    )
    (net (code "25") (name "/I_InA_3") (class "Default")
      (node (ref "J3") (pin "18") (pinfunction "18_18") (pintype "passive"))
    )
    (net (code "28") (name "/I_InB_1") (class "Default")
      (node (ref "J11") (pin "14") (pinfunction "14_14") (pintype "passive"))
    )
    (net (code "29") (name "/I_InB_2") (class "Default")
      (node (ref "J11") (pin "16") (pinfunction "16_16") (pintype "passive"))
    )
    (net (code "30") (name "/I_InB_3") (class "Default")
      (node (ref "J11") (pin "18") (pinfunction "18_18") (pintype "passive"))
    )
    (net (code "33") (name "/I_NegA_1") (class "Default")
      (node (ref "U5") (pin "6") (pinfunction "6_6") (pintype "passive"))
    )
    (net (code "34") (name "/I_NegA_2") (class "Default")
      (node (ref "U5") (pin "9") (pinfunction "9_9") (pintype "passive"))
    )
    (net (code "35") (name "/I_NegA_3") (class "Default")
      (node (ref "U5") (pin "13") (pinfunction "13_13") (pintype "passive"))
    )
    (net (code "38") (name "/I_NegB_1") (class "Default")
      (node (ref "U4") (pin "6") (pinfunction "6_6") (pintype "passive"))
    )
    (net (code "39") (name "/I_NegB_2") (class "Default")
      (node (ref "U4") (pin "9") (pinfunction "9_9") (pintype "passive"))
    )
    (net (code "40") (name "/I_NegB_3") (class "Default")
      (node (ref "U4") (pin "13") (pinfunction "13_13") (pintype "passive"))
    )
    (net (code "43") (name "/I_OutA_1") (class "Default")
      (node (ref "J1") (pin "39") (pinfunction "39_39") (pintype "passive"))
      (node (ref "TP13") (pin "1") (pinfunction "1_1") (pintype "passive"))
      (node (ref "U5") (pin "7") (pinfunction "7_7") (pintype "passive"))
    )
    (net (code "44") (name "/I_OutA_2") (class "Default")
      (node (ref "J1") (pin "41") (pinfunction "41_41") (pintype "passive"))
      (node (ref "TP14") (pin "1") (pinfunction "1_1") (pintype "passive"))
      (node (ref "U5") (pin "8") (pinfunction "8_8") (pintype "passive"))
    )
    (net (code "45") (name "/I_OutA_3") (class "Default")
      (node (ref "J1") (pin "43") (pinfunction "43_43") (pintype "passive"))
      (node (ref "TP15") (pin "1") (pinfunction "1_1") (pintype "passive"))
      (node (ref "U5") (pin "14") (pinfunction "14_14") (pintype "passive"))
    )
    (net (code "48") (name "/I_OutB_1") (class "Default")
      (node (ref "J1") (pin "05") (pinfunction "05_05") (pintype "passive"))
      (node (ref "TP2") (pin "1") (pinfunction "1_1") (pintype "passive"))
      (node (ref "U4") (pin "7") (pinfunction "7_7") (pintype "passive"))
    )
    (net (code "49") (name "/I_OutB_2") (class "Default")
      (node (ref "J1") (pin "07") (pinfunction "07_07") (pintype "passive"))
      (node (ref "TP3") (pin "1") (pinfunction "1_1") (pintype "passive"))
      (node (ref "U4") (pin "8") (pinfunction "8_8") (pintype "passive"))
    )
    (net (code "50") (name "/I_OutB_3") (class "Default")
      (node (ref "J1") (pin "03") (pinfunction "03_03") (pintype "passive"))
      (node (ref "TP1") (pin "1") (pinfunction "1_1") (pintype "passive"))
      (node (ref "U4") (pin "14") (pinfunction "14_14") (pintype "passive"))
    )
    (net (code "53") (name "/I_PosA_1") (class "Default")
      (node (ref "U5") (pin "5") (pinfunction "5_5") (pintype "passive"))
    )
    (net (code "54") (name "/I_PosA_2") (class "Default")
      (node (ref "U5") (pin "10") (pinfunction "10_10") (pintype "passive"))
    )
    (net (code "55") (name "/I_PosA_3") (class "Default")
      (node (ref "U5") (pin "12") (pinfunction "12_12") (pintype "passive"))
    )
    (net (code "58") (name "/I_PosB_1") (class "Default")
      (node (ref "U4") (pin "5") (pinfunction "5_5") (pintype "passive"))
    )
    (net (code "59") (name "/I_PosB_2") (class "Default")
      (node (ref "U4") (pin "10") (pinfunction "10_10") (pintype "passive"))
    )
    (net (code "60") (name "/I_PosB_3") (class "Default")
      (node (ref "U4") (pin "12") (pinfunction "12_12") (pintype "passive"))
    )
    (net (code "62") (name "/PCB_OT_1") (class "Default")
      (node (ref "J2") (pin "33") (pinfunction "33_33") (pintype "passive"))
      (node (ref "J4") (pin "13") (pinfunction "13_13") (pintype "passive"))
      (node (ref "TP17") (pin "1") (pinfunction "1_1") (pintype "passive"))
    )
    (net (code "63") (name "/PCB_OT_2") (class "Default")
      (node (ref "J12") (pin "13") (pinfunction "13_13") (pintype "passive"))
      (node (ref "J2") (pin "45") (pinfunction "45_45") (pintype "passive"))
      (node (ref "TP19") (pin "1") (pinfunction "1_1") (pintype "passive"))
    )
    (net (code "64") (name "/PWM_EN_1") (class "Default")
      (node (ref "J2") (pin "35") (pinfunction "35_35") (pintype "passive"))
      (node (ref "J4") (pin "16") (pinfunction "16_16") (pintype "passive"))
      (node (ref "TP18") (pin "1") (pinfunction "1_1") (pintype "passive"))
    )
    (net (code "65") (name "/PWM_EN_2") (class "Default")
      (node (ref "J12") (pin "16") (pinfunction "16_16") (pintype "passive"))
      (node (ref "J2") (pin "47") (pinfunction "47_47") (pintype "passive"))
      (node (ref "TP20") (pin "1") (pinfunction "1_1") (pintype "passive"))
    )
    (net (code "66") (name "/VDCA_In") (class "Default")
      (node (ref "J3") (pin "06") (pinfunction "06_06") (pintype "passive"))
      (node (ref "R9") (pin "1") (pinfunction "1_1") (pintype "passive"))
    )
    (net (code "67") (name "/VDCA_Out") (class "Default")
      (node (ref "J1") (pin "45") (pinfunction "45_45") (pintype "passive"))
      (node (ref "R6") (pin "1") (pinfunction "1_1") (pintype "passive"))
      (node (ref "TP16") (pin "1") (pinfunction "1_1") (pintype "passive"))
      (node (ref "U3") (pin "7") (pinfunction "7_7") (pintype "passive"))
    )
    (net (code "68") (name "/VDCB_In") (class "Default")
      (node (ref "J11") (pin "06") (pinfunction "06_06") (pintype "passive"))
      (node (ref "R15") (pin "1") (pinfunction "1_1") (pintype "passive"))
    )
    (net (code "69") (name "/VDCB_Out") (class "Default")
      (node (ref "J1") (pin "09") (pinfunction "09_09") (pintype "passive"))
      (node (ref "R12") (pin "1") (pinfunction "1_1") (pintype "passive"))
      (node (ref "TP4") (pin "1") (pinfunction "1_1") (pintype "passive"))
      (node (ref "U6") (pin "7") (pinfunction "7_7") (pintype "passive"))
    )
    (net (code "70") (name "/VREFA") (class "Default")
      (node (ref "J1") (pin "33") (pinfunction "33_33") (pintype "passive"))
      (node (ref "J3") (pin "20") (pinfunction "20_20") (pintype "passive"))
    )
    (net (code "72") (name "/V_capA_1") (class "Default")
      (node (ref "J1") (pin "27") (pinfunction "27_27") (pintype "passive"))
      (node (ref "TP9") (pin "1") (pinfunction "1_1") (pintype "passive"))
    )
    (net (code "73") (name "/V_capA_2") (class "Default")
      (node (ref "J1") (pin "29") (pinfunction "29_29") (pintype "passive"))
      (node (ref "TP10") (pin "1") (pinfunction "1_1") (pintype "passive"))
    )
    (net (code "74") (name "/V_capA_3") (class "Default")
      (node (ref "J1") (pin "31") (pinfunction "31_31") (pintype "passive"))
      (node (ref "TP11") (pin "1") (pinfunction "1_1") (pintype "passive"))
    )
    (net (code "77") (name "/V_capB_1") (class "Default")
      (node (ref "J1") (pin "17") (pinfunction "17_17") (pintype "passive"))
      (node (ref "TP6") (pin "1") (pinfunction "1_1") (pintype "passive"))
    )
    (net (code "78") (name "/V_capB_2") (class "Default")
      (node (ref "J1") (pin "19") (pinfunction "19_19") (pintype "passive"))
      (node (ref "TP7") (pin "1") (pinfunction "1_1") (pintype "passive"))
    )
    (net (code "79") (name "/V_capB_3") (class "Default")
      (node (ref "J1") (pin "21") (pinfunction "21_21") (pintype "passive"))
      (node (ref "TP8") (pin "1") (pinfunction "1_1") (pintype "passive"))
    )
    (net (code "82") (name "/V_o_outA_1") (class "Default")
      (node (ref "J6") (pin "3") (pinfunction "3_3") (pintype "passive"))
    )
    (net (code "83") (name "/V_o_outA_2") (class "Default")
      (node (ref "J6") (pin "2") (pinfunction "2_2") (pintype "passive"))
    )
    (net (code "84") (name "/V_o_outA_3") (class "Default")
      (node (ref "J6") (pin "1") (pinfunction "1_1") (pintype "passive"))
    )
    (net (code "87") (name "/V_o_outB_1") (class "Default")
      (node (ref "J8") (pin "3") (pinfunction "3_3") (pintype "passive"))
    )
    (net (code "88") (name "/V_o_outB_2") (class "Default")
      (node (ref "J8") (pin "2") (pinfunction "2_2") (pintype "passive"))
    )
    (net (code "89") (name "/V_o_outB_3") (class "Default")
      (node (ref "J8") (pin "1") (pinfunction "1_1") (pintype "passive"))
    )
    (net (code "92") (name "/V_termA_1") (class "Default")
      (node (ref "L1") (pin "4") (pinfunction "-_1_4") (pintype "passive"))
    )
    (net (code "93") (name "/V_termA_2") (class "Default")
      (node (ref "L1") (pin "5") (pinfunction "-_2_5") (pintype "passive"))
    )
    (net (code "94") (name "/V_termA_3") (class "Default")
      (node (ref "L1") (pin "6") (pinfunction "-_3_6") (pintype "passive"))
    )
    (net (code "97") (name "/V_termB_1") (class "Default")
      (node (ref "L2") (pin "4") (pinfunction "-_1_4") (pintype "passive"))
    )
    (net (code "98") (name "/V_termB_2") (class "Default")
      (node (ref "L2") (pin "5") (pinfunction "-_2_5") (pintype "passive"))
    )
    (net (code "99") (name "/V_termB_3") (class "Default")
      (node (ref "L2") (pin "6") (pinfunction "-_3_6") (pintype "passive"))
    )
    (net (code "101") (name "AGND") (class "Default")
      (node (ref "C10") (pin "1") (pinfunction "1_1") (pintype "passive"))
      (node (ref "C11") (pin "1") (pinfunction "1_1") (pintype "passive"))
      (node (ref "C12") (pin "1") (pinfunction "1_1") (pintype "passive"))
      (node (ref "C13") (pin "1") (pinfunction "1_1") (pintype "passive"))
      (node (ref "C14") (pin "1") (pinfunction "1_1") (pintype "passive"))
      (node (ref "C15") (pin "1") (pinfunction "1_1") (pintype "passive"))
      (node (ref "C16") (pin "1") (pinfunction "1_1") (pintype "passive"))
      (node (ref "C17") (pin "1") (pinfunction "1_1") (pintype "passive"))
      (node (ref "C18") (pin "1") (pinfunction "1_1") (pintype "passive"))
      (node (ref "C19") (pin "1") (pinfunction "1_1") (pintype "passive"))
      (node (ref "C2") (pin "1") (pinfunction "1_1") (pintype "passive"))
      (node (ref "C20") (pin "1") (pinfunction "1_1") (pintype "passive"))
      (node (ref "C21") (pin "1") (pinfunction "1_1") (pintype "passive"))
      (node (ref "C22") (pin "1") (pinfunction "1_1") (pintype "passive"))
      (node (ref "C23") (pin "1") (pinfunction "1_1") (pintype "passive"))
      (node (ref "C5") (pin "1") (pinfunction "1_1") (pintype "passive"))
      (node (ref "C7") (pin "1") (pinfunction "1_1") (pintype "passive"))
      (node (ref "C8") (pin "1") (pinfunction "1_1") (pintype "passive"))
      (node (ref "C9") (pin "1") (pinfunction "1_1") (pintype "passive"))
      (node (ref "J1") (pin "01") (pinfunction "01_01") (pintype "passive"))
      (node (ref "J1") (pin "02") (pinfunction "02_02") (pintype "passive"))
      (node (ref "J1") (pin "04") (pinfunction "04_04") (pintype "passive"))
      (node (ref "J1") (pin "06") (pinfunction "06_06") (pintype "passive"))
      (node (ref "J1") (pin "08") (pinfunction "08_08") (pintype "passive"))
      (node (ref "J1") (pin "10") (pinfunction "10_10") (pintype "passive"))
      (node (ref "J1") (pin "13") (pinfunction "13_13") (pintype "passive"))
      (node (ref "J1") (pin "14") (pinfunction "14_14") (pintype "passive"))
      (node (ref "J1") (pin "16") (pinfunction "16_16") (pintype "passive"))
      (node (ref "J1") (pin "18") (pinfunction "18_18") (pintype "passive"))
      (node (ref "J1") (pin "20") (pinfunction "20_20") (pintype "passive"))
      (node (ref "J1") (pin "22") (pinfunction "22_22") (pintype "passive"))
      (node (ref "J1") (pin "25") (pinfunction "25_25") (pintype "passive"))
      (node (ref "J1") (pin "26") (pinfunction "26_26") (pintype "passive"))
      (node (ref "J1") (pin "28") (pinfunction "28_28") (pintype "passive"))
      (node (ref "J1") (pin "30") (pinfunction "30_30") (pintype "passive"))
      (node (ref "J1") (pin "32") (pinfunction "32_32") (pintype "passive"))
      (node (ref "J1") (pin "34") (pinfunction "34_34") (pintype "passive"))
      (node (ref "J1") (pin "37") (pinfunction "37_37") (pintype "passive"))
      (node (ref "J1") (pin "38") (pinfunction "38_38") (pintype "passive"))
      (node (ref "J1") (pin "40") (pinfunction "40_40") (pintype "passive"))
      (node (ref "J1") (pin "42") (pinfunction "42_42") (pintype "passive"))
      (node (ref "J1") (pin "44") (pinfunction "44_44") (pintype "passive"))
      (node (ref "J1") (pin "46") (pinfunction "46_46") (pintype "passive"))
      (node (ref "J1") (pin "49") (pinfunction "49_49") (pintype "passive"))
      (node (ref "J1") (pin "50") (pinfunction "50_50") (pintype "passive"))
      (node (ref "J11") (pin "04") (pinfunction "04_04") (pintype "passive"))
      (node (ref "J12") (pin "02") (pinfunction "02_02") (pintype "passive"))
      (node (ref "J2") (pin "02") (pinfunction "02_02") (pintype "passive"))
      (node (ref "J2") (pin "04") (pinfunction "04_04") (pintype "passive"))
      (node (ref "J2") (pin "06") (pinfunction "06_06") (pintype "passive"))
      (node (ref "J2") (pin "08") (pinfunction "08_08") (pintype "passive"))
      (node (ref "J2") (pin "10") (pinfunction "10_10") (pintype "passive"))
      (node (ref "J2") (pin "12") (pinfunction "12_12") (pintype "passive"))
      (node (ref "J2") (pin "14") (pinfunction "14_14") (pintype "passive"))
      (node (ref "J2") (pin "16") (pinfunction "16_16") (pintype "passive"))
      (node (ref "J2") (pin "18") (pinfunction "18_18") (pintype "passive"))
      (node (ref "J2") (pin "20") (pinfunction "20_20") (pintype "passive"))
      (node (ref "J2") (pin "22") (pinfunction "22_22") (pintype "passive"))
      (node (ref "J2") (pin "24") (pinfunction "24_24") (pintype "passive"))
      (node (ref "J2") (pin "26") (pinfunction "26_26") (pintype "passive"))
      (node (ref "J2") (pin "28") (pinfunction "28_28") (pintype "passive"))
      (node (ref "J2") (pin "30") (pinfunction "30_30") (pintype "passive"))
      (node (ref "J2") (pin "32") (pinfunction "32_32") (pintype "passive"))
      (node (ref "J2") (pin "34") (pinfunction "34_34") (pintype "passive"))
      (node (ref "J2") (pin "36") (pinfunction "36_36") (pintype "passive"))
      (node (ref "J2") (pin "38") (pinfunction "38_38") (pintype "passive"))
      (node (ref "J2") (pin "40") (pinfunction "40_40") (pintype "passive"))
      (node (ref "J3") (pin "04") (pinfunction "04_04") (pintype "passive"))
      (node (ref "J4") (pin "02") (pinfunction "02_02") (pintype "passive"))
      (node (ref "R10") (pin "2") (pinfunction "2_2") (pintype "passive"))
      (node (ref "R13") (pin "1") (pinfunction "1_1") (pintype "passive"))
      (node (ref "R16") (pin "2") (pinfunction "2_2") (pintype "passive"))
      (node (ref "R7") (pin "1") (pinfunction "1_1") (pintype "passive"))
      (node (ref "TP35") (pin "1") (pinfunction "1_1") (pintype "passive"))
    )
    (net (code "104") (name "Net-(C4-Pad1)") (class "Default")
      (node (ref "C4") (pin "1") (pinfunction "1_1") (pintype "passive"))
      (node (ref "C5") (pin "2") (pinfunction "2_2") (pintype "passive"))
      (node (ref "R5") (pin "1") (pinfunction "1_1") (pintype "passive"))
      (node (ref "R7") (pin "2") (pinfunction "2_2") (pintype "passive"))
      (node (ref "U3") (pin "3") (pinfunction "3_3") (pintype "passive"))
      (node (ref "U5") (pin "3") (pinfunction "3_3") (pintype "passive"))
    )
    (net (code "105") (name "Net-(C6-Pad1)") (class "Default")
      (node (ref "C6") (pin "1") (pinfunction "1_1") (pintype "passive"))
      (node (ref "C7") (pin "2") (pinfunction "2_2") (pintype "passive"))
      (node (ref "R11") (pin "1") (pinfunction "1_1") (pintype "passive"))
      (node (ref "R13") (pin "2") (pinfunction "2_2") (pintype "passive"))
      (node (ref "U4") (pin "3") (pinfunction "3_3") (pintype "passive"))
      (node (ref "U6") (pin "3") (pinfunction "3_3") (pintype "passive"))
    )
    (net (code "106") (name "Net-(L1-+_1)") (class "Default")
      (node (ref "J7") (pin "3") (pinfunction "3_3") (pintype "passive"))
      (node (ref "L1") (pin "1") (pinfunction "+_1_1") (pintype "passive"))
    )
    (net (code "107") (name "Net-(L1-+_2)") (class "Default")
      (node (ref "J7") (pin "2") (pinfunction "2_2") (pintype "passive"))
      (node (ref "L1") (pin "2") (pinfunction "+_2_2") (pintype "passive"))
    )
    (net (code "108") (name "Net-(L1-+_3)") (class "Default")
      (node (ref "J7") (pin "1") (pinfunction "1_1") (pintype "passive"))
      (node (ref "L1") (pin "3") (pinfunction "+_3_3") (pintype "passive"))
    )
    (net (code "109") (name "Net-(L2-+_1)") (class "Default")
      (node (ref "J9") (pin "3") (pinfunction "3_3") (pintype "passive"))
      (node (ref "L2") (pin "1") (pinfunction "+_1_1") (pintype "passive"))
    )
    (net (code "110") (name "Net-(L2-+_2)") (class "Default")
      (node (ref "J9") (pin "2") (pinfunction "2_2") (pintype "passive"))
      (node (ref "L2") (pin "2") (pinfunction "+_2_2") (pintype "passive"))
    )
    (net (code "111") (name "Net-(L2-+_3)") (class "Default")
      (node (ref "J9") (pin "1") (pinfunction "1_1") (pintype "passive"))
      (node (ref "L2") (pin "3") (pinfunction "+_3_3") (pintype "passive"))
    )
    (net (code "112") (name "Net-(R6-Pad2)") (class "Default")
      (node (ref "R6") (pin "2") (pinfunction "2_2") (pintype "passive"))
      (node (ref "R8") (pin "2") (pinfunction "2_2") (pintype "passive"))
      (node (ref "U3") (pin "6") (pinfunction "6_6") (pintype "passive"))
    )
    (net (code "113") (name "Net-(R10-Pad1)") (class "Default")
      (node (ref "R10") (pin "1") (pinfunction "1_1") (pintype "passive"))
      (node (ref "R9") (pin "2") (pinfunction "2_2") (pintype "passive"))
      (node (ref "U3") (pin "5") (pinfunction "5_5") (pintype "passive"))
    )
    (net (code "114") (name "Net-(R12-Pad2)") (class "Default")
      (node (ref "R12") (pin "2") (pinfunction "2_2") (pintype "passive"))
      (node (ref "R14") (pin "2") (pinfunction "2_2") (pintype "passive"))
      (node (ref "U6") (pin "6") (pinfunction "6_6") (pintype "passive"))
    )
    (net (code "115") (name "Net-(R15-Pad2)") (class "Default")
      (node (ref "R15") (pin "2") (pinfunction "2_2") (pintype "passive"))
      (node (ref "R16") (pin "1") (pinfunction "1_1") (pintype "passive"))
      (node (ref "U6") (pin "5") (pinfunction "5_5") (pintype "passive"))
    )
    (net (code "116") (name "unconnected-(J2-Pad25)") (class "Default")
      (node (ref "J2") (pin "25") (pinfunction "25_25") (pintype "passive"))
    )
    (net (code "117") (name "unconnected-(J2-Pad27)") (class "Default")
      (node (ref "J2") (pin "27") (pinfunction "27_27") (pintype "passive"))
    )
    (net (code "118") (name "unconnected-(J2-Pad29)") (class "Default")
      (node (ref "J2") (pin "29") (pinfunction "29_29") (pintype "passive"))
    )
    (net (code "119") (name "unconnected-(J2-Pad31)") (class "Default")
      (node (ref "J2") (pin "31") (pinfunction "31_31") (pintype "passive"))
    )
    (net (code "120") (name "unconnected-(J2-Pad37)") (class "Default")
      (node (ref "J2") (pin "37") (pinfunction "37_37") (pintype "passive"))
    )
    (net (code "121") (name "unconnected-(J2-Pad39)") (class "Default")
      (node (ref "J2") (pin "39") (pinfunction "39_39") (pintype "passive"))
    )
    (net (code "122") (name "unconnected-(J2-Pad41)") (class "Default")
      (node (ref "J2") (pin "41") (pinfunction "41_41") (pintype "passive"))
    )
    (net (code "123") (name "unconnected-(J2-Pad42)") (class "Default")
      (node (ref "J2") (pin "42") (pinfunction "42_42") (pintype "passive"))
    )
    (net (code "124") (name "unconnected-(J2-Pad43)") (class "Default")
      (node (ref "J2") (pin "43") (pinfunction "43_43") (pintype "passive"))
    )
    (net (code "125") (name "unconnected-(J2-Pad44)") (class "Default")
      (node (ref "J2") (pin "44") (pinfunction "44_44") (pintype "passive"))
    )
    (net (code "126") (name "unconnected-(J2-Pad46)") (class "Default")
      (node (ref "J2") (pin "46") (pinfunction "46_46") (pintype "passive"))
    )
    (net (code "127") (name "unconnected-(J2-Pad48)") (class "Default")
      (node (ref "J2") (pin "48") (pinfunction "48_48") (pintype "passive"))
    )
    (net (code "128") (name "unconnected-(J2-Pad49)") (class "Default")
      (node (ref "J2") (pin "49") (pinfunction "49_49") (pintype "passive"))
    )
    (net (code "129") (name "unconnected-(J2-Pad50)") (class "Default")
      (node (ref "J2") (pin "50") (pinfunction "50_50") (pintype "passive"))
    )
    (net (code "130") (name "unconnected-(J3-Pad01)") (class "Default")
      (node (ref "J3") (pin "01") (pinfunction "01_01") (pintype "passive"))
    )
    (net (code "131") (name "unconnected-(J3-Pad02)") (class "Default")
      (node (ref "J3") (pin "02") (pinfunction "02_02") (pintype "passive"))
    )
    (net (code "132") (name "unconnected-(J3-Pad03)") (class "Default")
      (node (ref "J3") (pin "03") (pinfunction "03_03") (pintype "passive"))
    )
    (net (code "133") (name "unconnected-(J3-Pad05)") (class "Default")
      (node (ref "J3") (pin "05") (pinfunction "05_05") (pintype "passive"))
    )
    (net (code "134") (name "unconnected-(J3-Pad07)") (class "Default")
      (node (ref "J3") (pin "07") (pinfunction "07_07") (pintype "passive"))
    )
    (net (code "135") (name "unconnected-(J3-Pad08)") (class "Default")
      (node (ref "J3") (pin "08") (pinfunction "08_08") (pintype "passive"))
    )
    (net (code "136") (name "unconnected-(J3-Pad09)") (class "Default")
      (node (ref "J3") (pin "09") (pinfunction "09_09") (pintype "passive"))
    )
    (net (code "137") (name "unconnected-(J3-Pad10)") (class "Default")
      (node (ref "J3") (pin "10") (pinfunction "10_10") (pintype "passive"))
    )
    (net (code "138") (name "unconnected-(J3-Pad12)") (class "Default")
      (node (ref "J3") (pin "12") (pinfunction "12_12") (pintype "passive"))
    )
    (net (code "139") (name "unconnected-(J3-Pad13)") (class "Default")
      (node (ref "J3") (pin "13") (pinfunction "13_13") (pintype "passive"))
    )
    (net (code "140") (name "unconnected-(J3-Pad15)") (class "Default")
      (node (ref "J3") (pin "15") (pinfunction "15_15") (pintype "passive"))
    )
    (net (code "141") (name "unconnected-(J3-Pad17)") (class "Default")
      (node (ref "J3") (pin "17") (pinfunction "17_17") (pintype "passive"))
    )
    (net (code "142") (name "unconnected-(J3-Pad19)") (class "Default")
      (node (ref "J3") (pin "19") (pinfunction "19_19") (pintype "passive"))
    )
    (net (code "143") (name "unconnected-(J4-Pad04)") (class "Default")
      (node (ref "J4") (pin "04") (pinfunction "04_04") (pintype "passive"))
    )
    (net (code "144") (name "unconnected-(J4-Pad06)") (class "Default")
      (node (ref "J4") (pin "06") (pinfunction "06_06") (pintype "passive"))
    )
    (net (code "145") (name "unconnected-(J4-Pad08)") (class "Default")
      (node (ref "J4") (pin "08") (pinfunction "08_08") (pintype "passive"))
    )
    (net (code "146") (name "unconnected-(J4-Pad10)") (class "Default")
      (node (ref "J4") (pin "10") (pinfunction "10_10") (pintype "passive"))
    )
    (net (code "147") (name "unconnected-(J4-Pad12)") (class "Default")
      (node (ref "J4") (pin "12") (pinfunction "12_12") (pintype "passive"))
    )
    (net (code "148") (name "unconnected-(J4-Pad14)") (class "Default")
      (node (ref "J4") (pin "14") (pinfunction "14_14") (pintype "passive"))
    )
    (net (code "149") (name "unconnected-(J4-Pad15)") (class "Default")
      (node (ref "J4") (pin "15") (pinfunction "15_15") (pintype "passive"))
    )
    (net (code "150") (name "unconnected-(J4-Pad17)") (class "Default")
      (node (ref "J4") (pin "17") (pinfunction "17_17") (pintype "passive"))
    )
    (net (code "151") (name "unconnected-(J4-Pad18)") (class "Default")
      (node (ref "J4") (pin "18") (pinfunction "18_18") (pintype "passive"))
    )
    (net (code "152") (name "unconnected-(J4-Pad19)") (class "Default")
      (node (ref "J4") (pin "19") (pinfunction "19_19") (pintype "passive"))
    )
    (net (code "153") (name "unconnected-(J4-Pad20)") (class "Default")
      (node (ref "J4") (pin "20") (pinfunction "20_20") (pintype "passive"))
    )
    (net (code "154") (name "unconnected-(J5-Pad1)") (class "Default")
      (node (ref "J5") (pin "1") (pinfunction "1_1") (pintype "passive"))
    )
    (net (code "155") (name "unconnected-(J10-Pad1)") (class "Default")
      (node (ref "J10") (pin "1") (pinfunction "1_1") (pintype "passive"))
    )
    (net (code "156") (name "unconnected-(J11-Pad01)") (class "Default")
      (node (ref "J11") (pin "01") (pinfunction "01_01") (pintype "passive"))
    )
    (net (code "157") (name "unconnected-(J11-Pad02)") (class "Default")
      (node (ref "J11") (pin "02") (pinfunction "02_02") (pintype "passive"))
    )
    (net (code "158") (name "unconnected-(J11-Pad03)") (class "Default")
      (node (ref "J11") (pin "03") (pinfunction "03_03") (pintype "passive"))
    )
    (net (code "159") (name "unconnected-(J11-Pad05)") (class "Default")
      (node (ref "J11") (pin "05") (pinfunction "05_05") (pintype "passive"))
    )
    (net (code "160") (name "unconnected-(J11-Pad07)") (class "Default")
      (node (ref "J11") (pin "07") (pinfunction "07_07") (pintype "passive"))
    )
    (net (code "161") (name "unconnected-(J11-Pad08)") (class "Default")
      (node (ref "J11") (pin "08") (pinfunction "08_08") (pintype "passive"))
    )
    (net (code "162") (name "unconnected-(J11-Pad09)") (class "Default")
      (node (ref "J11") (pin "09") (pinfunction "09_09") (pintype "passive"))
    )
    (net (code "163") (name "unconnected-(J11-Pad10)") (class "Default")
      (node (ref "J11") (pin "10") (pinfunction "10_10") (pintype "passive"))
    )
    (net (code "164") (name "unconnected-(J11-Pad12)") (class "Default")
      (node (ref "J11") (pin "12") (pinfunction "12_12") (pintype "passive"))
    )
    (net (code "165") (name "unconnected-(J11-Pad13)") (class "Default")
      (node (ref "J11") (pin "13") (pinfunction "13_13") (pintype "passive"))
    )
    (net (code "166") (name "unconnected-(J11-Pad15)") (class "Default")
      (node (ref "J11") (pin "15") (pinfunction "15_15") (pintype "passive"))
    )
    (net (code "167") (name "unconnected-(J11-Pad17)") (class "Default")
      (node (ref "J11") (pin "17") (pinfunction "17_17") (pintype "passive"))
    )
    (net (code "168") (name "unconnected-(J11-Pad19)") (class "Default")
      (node (ref "J11") (pin "19") (pinfunction "19_19") (pintype "passive"))
    )
    (net (code "169") (name "unconnected-(J11-Pad20)") (class "Default")
      (node (ref "J11") (pin "20") (pinfunction "20_20") (pintype "passive"))
    )
    (net (code "170") (name "unconnected-(J12-Pad04)") (class "Default")
      (node (ref "J12") (pin "04") (pinfunction "04_04") (pintype "passive"))
    )
    (net (code "171") (name "unconnected-(J12-Pad06)") (class "Default")
      (node (ref "J12") (pin "06") (pinfunction "06_06") (pintype "passive"))
    )
    (net (code "172") (name "unconnected-(J12-Pad08)") (class "Default")
      (node (ref "J12") (pin "08") (pinfunction "08_08") (pintype "passive"))
    )
    (net (code "173") (name "unconnected-(J12-Pad10)") (class "Default")
      (node (ref "J12") (pin "10") (pinfunction "10_10") (pintype "passive"))
    )
    (net (code "174") (name "unconnected-(J12-Pad12)") (class "Default")
      (node (ref "J12") (pin "12") (pinfunction "12_12") (pintype "passive"))
    )
    (net (code "175") (name "unconnected-(J12-Pad14)") (class "Default")
      (node (ref "J12") (pin "14") (pinfunction "14_14") (pintype "passive"))
    )
    (net (code "176") (name "unconnected-(J12-Pad15)") (class "Default")
      (node (ref "J12") (pin "15") (pinfunction "15_15") (pintype "passive"))
    )
    (net (code "177") (name "unconnected-(J12-Pad17)") (class "Default")
      (node (ref "J12") (pin "17") (pinfunction "17_17") (pintype "passive"))
    )
    (net (code "178") (name "unconnected-(J12-Pad18)") (class "Default")
      (node (ref "J12") (pin "18") (pinfunction "18_18") (pintype "passive"))
    )
    (net (code "179") (name "unconnected-(J12-Pad19)") (class "Default")
      (node (ref "J12") (pin "19") (pinfunction "19_19") (pintype "passive"))
    )
    (net (code "180") (name "unconnected-(J12-Pad20)") (class "Default")
      (node (ref "J12") (pin "20") (pinfunction "20_20") (pintype "passive"))
    )
    (net (code "181") (name "unconnected-(J13-Pad1)") (class "Default")
      (node (ref "J13") (pin "1") (pinfunction "1_1") (pintype "passive"))
    )
    (net (code "182") (name "unconnected-(J14-Pad1)") (class "Default")
      (node (ref "J14") (pin "1") (pinfunction "1_1") (pintype "passive"))
    )
    (net (code "183") (name "unconnected-(J15-Pad1)") (class "Default")
      (node (ref "J15") (pin "1") (pinfunction "1_1") (pintype "passive"))
    )
    (net (code "184") (name "unconnected-(J16-Pad1)") (class "Default")
      (node (ref "J16") (pin "1") (pinfunction "1_1") (pintype "passive"))
    )
    (net (code "185") (name "unconnected-(J17-Pad1)") (class "Default")
      (node (ref "J17") (pin "1") (pinfunction "1_1") (pintype "passive"))
    )
    (net (code "186") (name "unconnected-(J19-Pad1)") (class "Default")
      (node (ref "J19") (pin "1") (pinfunction "1_1") (pintype "passive"))
    )
    (net (code "187") (name "unconnected-(J20-Pad1)") (class "Default")
      (node (ref "J20") (pin "1") (pinfunction "1_1") (pintype "passive"))
    )
    (net (code "188") (name "unconnected-(U3-Pad8)") (class "Default")
      (node (ref "U3") (pin "8") (pinfunction "8_8") (pintype "passive"))
    )
    (net (code "189") (name "unconnected-(U3-Pad9)") (class "Default")
      (node (ref "U3") (pin "9") (pinfunction "9_9") (pintype "passive"))
    )
    (net (code "190") (name "unconnected-(U3-Pad10)") (class "Default")
      (node (ref "U3") (pin "10") (pinfunction "10_10") (pintype "passive"))
    )
    (net (code "191") (name "unconnected-(U3-Pad12)") (class "Default")
      (node (ref "U3") (pin "12") (pinfunction "12_12") (pintype "passive"))
    )
    (net (code "192") (name "unconnected-(U3-Pad13)") (class "Default")
      (node (ref "U3") (pin "13") (pinfunction "13_13") (pintype "passive"))
    )
    (net (code "193") (name "unconnected-(U3-Pad14)") (class "Default")
      (node (ref "U3") (pin "14") (pinfunction "14_14") (pintype "passive"))
    )
    (net (code "194") (name "unconnected-(U6-Pad8)") (class "Default")
      (node (ref "U6") (pin "8") (pinfunction "8_8") (pintype "passive"))
    )
    (net (code "195") (name "unconnected-(U6-Pad9)") (class "Default")
      (node (ref "U6") (pin "9") (pinfunction "9_9") (pintype "passive"))
    )
    (net (code "196") (name "unconnected-(U6-Pad10)") (class "Default")
      (node (ref "U6") (pin "10") (pinfunction "10_10") (pintype "passive"))
    )
    (net (code "197") (name "unconnected-(U6-Pad12)") (class "Default")
      (node (ref "U6") (pin "12") (pinfunction "12_12") (pintype "passive"))
    )
    (net (code "198") (name "unconnected-(U6-Pad13)") (class "Default")
      (node (ref "U6") (pin "13") (pinfunction "13_13") (pintype "passive"))
    )
    (net (code "199") (name "unconnected-(U6-Pad14)") (class "Default")
      (node (ref "U6") (pin "14") (pinfunction "14_14") (pintype "passive"))
    )
  )
)
